# 4-SSR.net
KiCad netlist of a schematic drawn in EAGLE
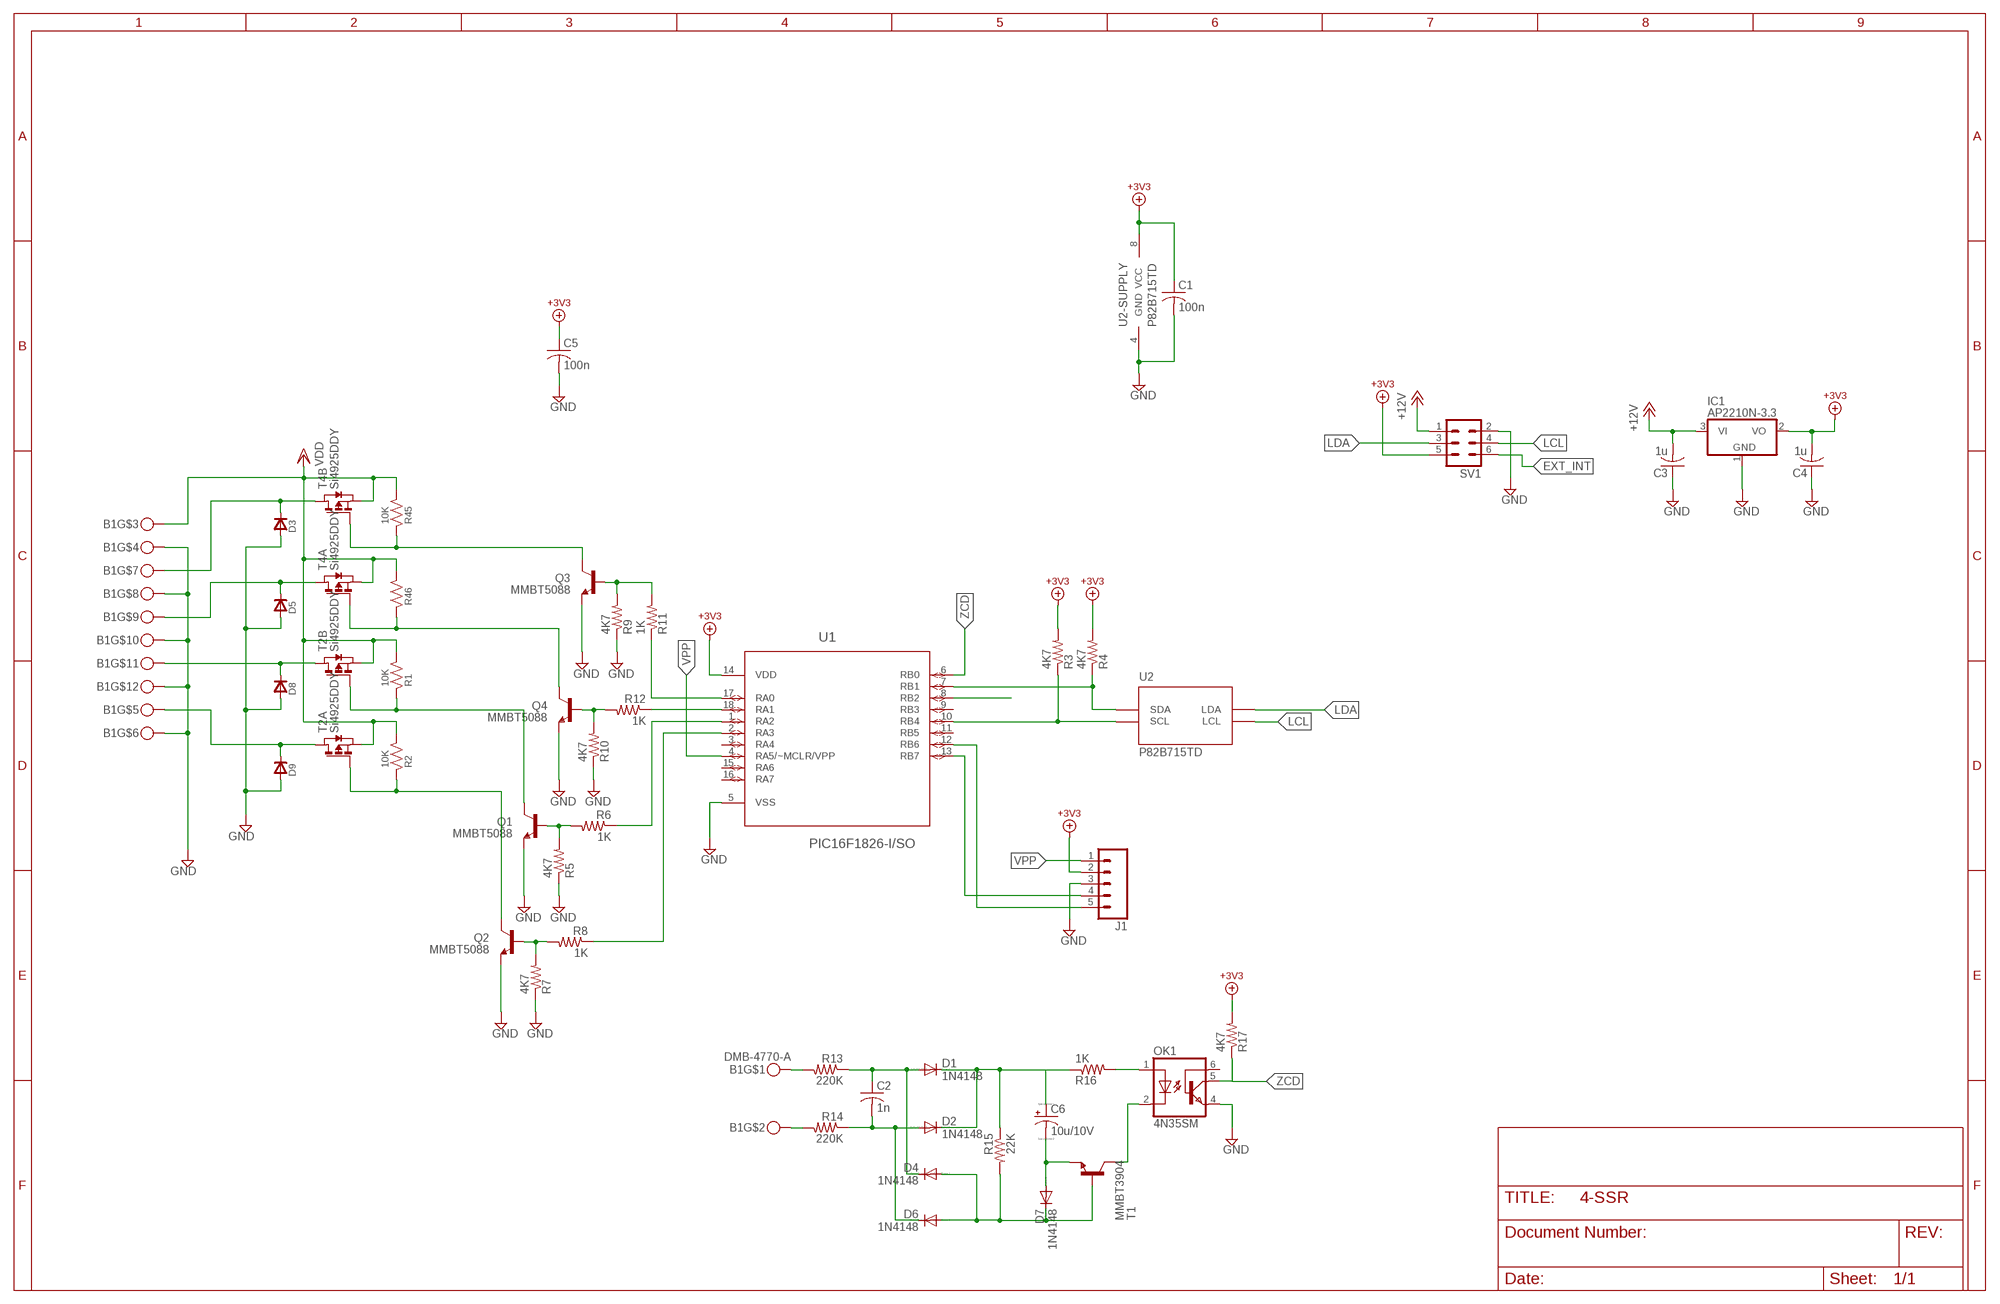
[diagram p0: schematic, sheet 1]

(export (version "E")
  (design (tool "Eeschema 10.0.6"))
  (components
    (comp (ref "B1")
      (value "DMB-4770-A")
      (footprint "eagle-import:DMB-4770-A-PKG")
      (libsource (lib "eagle-import") (part "DMB-4770-A"))
    )
    (comp (ref "C1")
      (value "100n")
      (footprint "eagle-import:C0805")
      (libsource (lib "eagle-import") (part "C-USC0805"))
    )
    (comp (ref "C2")
      (value "1n")
      (footprint "eagle-import:C1808")
      (libsource (lib "eagle-import") (part "C-USC1808"))
    )
    (comp (ref "C3")
      (value "1u")
      (footprint "eagle-import:C0805")
      (libsource (lib "eagle-import") (part "C-USC0805"))
    )
    (comp (ref "C4")
      (value "1u")
      (footprint "eagle-import:C0805")
      (libsource (lib "eagle-import") (part "C-USC0805"))
    )
    (comp (ref "C5")
      (value "100n")
      (footprint "eagle-import:C0805")
      (libsource (lib "eagle-import") (part "C-USC0805"))
    )
    (comp (ref "C6")
      (value "10u/10V")
      (footprint "eagle-import:PANASONIC_B")
      (libsource (lib "eagle-import") (part "CPOL-USB"))
    )
    (comp (ref "D1")
      (value "1N4148")
      (footprint "eagle-import:SOD80C")
      (libsource (lib "eagle-import") (part "DIODE-SOD80C"))
    )
    (comp (ref "D2")
      (value "1N4148")
      (footprint "eagle-import:SOD80C")
      (libsource (lib "eagle-import") (part "DIODE-SOD80C"))
    )
    (comp (ref "D3")
      (value "DSMA")
      (footprint "eagle-import:DSMA")
      (libsource (lib "eagle-import") (part "DSMA"))
    )
    (comp (ref "D4")
      (value "1N4148")
      (footprint "eagle-import:SOD80C")
      (libsource (lib "eagle-import") (part "DIODE-SOD80C"))
    )
    (comp (ref "D5")
      (value "DSMA")
      (footprint "eagle-import:DSMA")
      (libsource (lib "eagle-import") (part "DSMA"))
    )
    (comp (ref "D6")
      (value "1N4148")
      (footprint "eagle-import:SOD80C")
      (libsource (lib "eagle-import") (part "DIODE-SOD80C"))
    )
    (comp (ref "D7")
      (value "1N4148")
      (footprint "eagle-import:SOD80C")
      (libsource (lib "eagle-import") (part "DIODE-SOD80C"))
    )
    (comp (ref "D8")
      (value "DSMA")
      (footprint "eagle-import:DSMA")
      (libsource (lib "eagle-import") (part "DSMA"))
    )
    (comp (ref "D9")
      (value "DSMA")
      (footprint "eagle-import:DSMA")
      (libsource (lib "eagle-import") (part "DSMA"))
    )
    (comp (ref "IC1")
      (value "AP2210N-3.3")
      (footprint "eagle-import:SOT23")
      (libsource (lib "eagle-import") (part "MCP1703CB"))
    )
    (comp (ref "J1")
      (value "M05PTH")
      (footprint "eagle-import:1X05")
      (libsource (lib "eagle-import") (part "M05PTH"))
    )
    (comp (ref "OK1")
      (value "4N35SM")
      (footprint "eagle-import:DIL6-SMD")
      (fields (field (name "MF") "FAIRCHILD SEMICONDUCTOR") (field (name "MPN") "4N35S-M"))
      (libsource (lib "eagle-import") (part "4N?MS35"))
    )
    (comp (ref "Q1")
      (value "MMBT5088")
      (footprint "eagle-import:SOT23-3")
      (libsource (lib "eagle-import") (part "TRANSISTOR_NPNMMBT5088"))
    )
    (comp (ref "Q2")
      (value "MMBT5088")
      (footprint "eagle-import:SOT23-3")
      (libsource (lib "eagle-import") (part "TRANSISTOR_NPNMMBT5088"))
    )
    (comp (ref "Q3")
      (value "MMBT5088")
      (footprint "eagle-import:SOT23-3")
      (libsource (lib "eagle-import") (part "TRANSISTOR_NPNMMBT5088"))
    )
    (comp (ref "Q4")
      (value "MMBT5088")
      (footprint "eagle-import:SOT23-3")
      (libsource (lib "eagle-import") (part "TRANSISTOR_NPNMMBT5088"))
    )
    (comp (ref "R1")
      (value "10K")
      (footprint "eagle-import:R0805")
      (libsource (lib "eagle-import") (part "RU0805"))
    )
    (comp (ref "R2")
      (value "10K")
      (footprint "eagle-import:R0805")
      (libsource (lib "eagle-import") (part "RU0805"))
    )
    (comp (ref "R3")
      (value "4K7")
      (footprint "eagle-import:R0805")
      (libsource (lib "eagle-import") (part "resistor_R-US_R0805"))
    )
    (comp (ref "R4")
      (value "4K7")
      (footprint "eagle-import:R0805")
      (libsource (lib "eagle-import") (part "resistor_R-US_R0805"))
    )
    (comp (ref "R5")
      (value "4K7")
      (footprint "eagle-import:R0805")
      (libsource (lib "eagle-import") (part "resistor_R-US_R0805"))
    )
    (comp (ref "R6")
      (value "1K")
      (footprint "eagle-import:R0805")
      (libsource (lib "eagle-import") (part "resistor_R-US_R0805"))
    )
    (comp (ref "R7")
      (value "4K7")
      (footprint "eagle-import:R0805")
      (libsource (lib "eagle-import") (part "resistor_R-US_R0805"))
    )
    (comp (ref "R8")
      (value "1K")
      (footprint "eagle-import:R0805")
      (libsource (lib "eagle-import") (part "resistor_R-US_R0805"))
    )
    (comp (ref "R9")
      (value "4K7")
      (footprint "eagle-import:R0805")
      (libsource (lib "eagle-import") (part "resistor_R-US_R0805"))
    )
    (comp (ref "R10")
      (value "4K7")
      (footprint "eagle-import:R0805")
      (libsource (lib "eagle-import") (part "resistor_R-US_R0805"))
    )
    (comp (ref "R11")
      (value "1K")
      (footprint "eagle-import:R0805")
      (libsource (lib "eagle-import") (part "resistor_R-US_R0805"))
    )
    (comp (ref "R12")
      (value "1K")
      (footprint "eagle-import:R0805")
      (libsource (lib "eagle-import") (part "resistor_R-US_R0805"))
    )
    (comp (ref "R13")
      (value "220K")
      (footprint "eagle-import:R0805")
      (libsource (lib "eagle-import") (part "R-US_R0805"))
    )
    (comp (ref "R14")
      (value "220K")
      (footprint "eagle-import:R0805")
      (libsource (lib "eagle-import") (part "R-US_R0805"))
    )
    (comp (ref "R15")
      (value "22K")
      (footprint "eagle-import:R0805")
      (libsource (lib "eagle-import") (part "R-US_R0805"))
    )
    (comp (ref "R16")
      (value "1K")
      (footprint "eagle-import:R0805")
      (libsource (lib "eagle-import") (part "R-US_R0805"))
    )
    (comp (ref "R17")
      (value "4K7")
      (footprint "eagle-import:R0805")
      (libsource (lib "eagle-import") (part "resistor_R-US_R0805"))
    )
    (comp (ref "R45")
      (value "10K")
      (footprint "eagle-import:R0805")
      (libsource (lib "eagle-import") (part "RU0805"))
    )
    (comp (ref "R46")
      (value "RU0805")
      (footprint "eagle-import:R0805")
      (libsource (lib "eagle-import") (part "RU0805"))
    )
    (comp (ref "SV1")
      (value "ML6")
      (footprint "eagle-import:ML6")
      (libsource (lib "eagle-import") (part "ML6"))
    )
    (comp (ref "T1")
      (value "MMBT3904")
      (footprint "eagle-import:SOT23-BEC")
      (libsource (lib "eagle-import") (part "-NPN-SOT23-BECMMBT3904LT1"))
    )
    (comp (ref "T2")
      (value "Si4925DDY")
      (footprint "eagle-import:SO8")
      (libsource (lib "eagle-import") (part "PMOS2SO8"))
    )
    (comp (ref "T4")
      (value "Si4925DDY")
      (footprint "eagle-import:SO8")
      (libsource (lib "eagle-import") (part "PMOS2SO8"))
    )
    (comp (ref "U1")
      (value "PIC16F1826-I/SO")
      (footprint "eagle-import:SOIC127P1030X175-18N")
      (libsource (lib "eagle-import") (part "PIC16F1826-I/SO"))
    )
    (comp (ref "U2")
      (value "P82B715TD")
      (footprint "eagle-import:SOIC-8")
      (fields (field (name "MANUFACTURER") "NXP Semiconductors") (field (name "PART_NUMBER") "P82B715TD,118"))
      (libsource (lib "eagle-import") (part "P82B715?TD"))
    )
  )
  (nets
    (net (code "1") (name "+12V") (class "Default")
      (node (ref "C3") (pin "2") (pinfunction "2_2") (pintype "passive"))
      (node (ref "IC1") (pin "3") (pinfunction "VI_3") (pintype "input"))
      (node (ref "SV1") (pin "1") (pinfunction "1_1") (pintype "passive"))
    )
    (net (code "2") (name "EXT_INT") (class "Default")
      (node (ref "SV1") (pin "6") (pinfunction "6_6") (pintype "passive"))
    )
    (net (code "3") (name "GND") (class "Default")
      (node (ref "B1") (pin "P$10") (pinfunction "KL_P$10") (pintype "passive"))
      (node (ref "B1") (pin "P$12") (pinfunction "KL_P$12") (pintype "passive"))
      (node (ref "B1") (pin "P$4") (pinfunction "KL_P$4") (pintype "passive"))
      (node (ref "B1") (pin "P$6") (pinfunction "KL_P$6") (pintype "passive"))
      (node (ref "B1") (pin "P$8") (pinfunction "KL_P$8") (pintype "passive"))
      (node (ref "C1") (pin "2") (pinfunction "2_2") (pintype "passive"))
      (node (ref "C3") (pin "1") (pinfunction "1_1") (pintype "passive"))
      (node (ref "C4") (pin "1") (pinfunction "1_1") (pintype "passive"))
      (node (ref "C5") (pin "2") (pinfunction "2_2") (pintype "passive"))
      (node (ref "D3") (pin "A") (pinfunction "A_A") (pintype "passive"))
      (node (ref "D5") (pin "A") (pinfunction "A_A") (pintype "passive"))
      (node (ref "D8") (pin "A") (pinfunction "A_A") (pintype "passive"))
      (node (ref "D9") (pin "A") (pinfunction "A_A") (pintype "passive"))
      (node (ref "IC1") (pin "1") (pinfunction "GND_1") (pintype "passive"))
      (node (ref "J1") (pin "3") (pinfunction "3_3") (pintype "passive"))
      (node (ref "OK1") (pin "4") (pinfunction "EMI_4") (pintype "passive"))
      (node (ref "Q1") (pin "2") (pinfunction "E_2") (pintype "passive"))
      (node (ref "Q2") (pin "2") (pinfunction "E_2") (pintype "passive"))
      (node (ref "Q3") (pin "2") (pinfunction "E_2") (pintype "passive"))
      (node (ref "Q4") (pin "2") (pinfunction "E_2") (pintype "passive"))
      (node (ref "R10") (pin "1") (pinfunction "1_1") (pintype "passive"))
      (node (ref "R5") (pin "1") (pinfunction "1_1") (pintype "passive"))
      (node (ref "R7") (pin "1") (pinfunction "1_1") (pintype "passive"))
      (node (ref "R9") (pin "1") (pinfunction "1_1") (pintype "passive"))
      (node (ref "SV1") (pin "2") (pinfunction "2_2") (pintype "passive"))
      (node (ref "U1") (pin "5") (pinfunction "VSS_5") (pintype "power_in"))
      (node (ref "U2") (pin "4") (pinfunction "GND_4") (pintype "bidirectional"))
    )
    (net (code "4") (name "LCL") (class "Default")
      (node (ref "SV1") (pin "4") (pinfunction "4_4") (pintype "passive"))
      (node (ref "U2") (pin "2") (pinfunction "LCL_2") (pintype "bidirectional"))
    )
    (net (code "5") (name "LDA") (class "Default")
      (node (ref "SV1") (pin "3") (pinfunction "3_3") (pintype "passive"))
      (node (ref "U2") (pin "7") (pinfunction "LDA_7") (pintype "bidirectional"))
    )
    (net (code "6") (name "Net-(B1A-KL)") (class "Default")
      (node (ref "B1") (pin "P$1") (pinfunction "KL_P$1") (pintype "passive"))
      (node (ref "R13") (pin "2") (pinfunction "2_2") (pintype "passive"))
    )
    (net (code "7") (name "Net-(B1C-KL)") (class "Default")
      (node (ref "B1") (pin "P$11") (pinfunction "KL_P$11") (pintype "passive"))
      (node (ref "D8") (pin "C") (pinfunction "C_C") (pintype "passive"))
      (node (ref "T2") (pin "5") (pinfunction "D_5") (pintype "passive"))
      (node (ref "T2") (pin "6") (pinfunction "D_6") (pintype "passive"))
    )
    (net (code "8") (name "Net-(B1E-KL)") (class "Default")
      (node (ref "B1") (pin "P$2") (pinfunction "KL_P$2") (pintype "passive"))
      (node (ref "R14") (pin "2") (pinfunction "2_2") (pintype "passive"))
    )
    (net (code "9") (name "Net-(B1H-KL)") (class "Default")
      (node (ref "B1") (pin "P$5") (pinfunction "KL_P$5") (pintype "passive"))
      (node (ref "D9") (pin "C") (pinfunction "C_C") (pintype "passive"))
      (node (ref "T2") (pin "7") (pinfunction "D_7") (pintype "passive"))
      (node (ref "T2") (pin "8") (pinfunction "D_8") (pintype "passive"))
    )
    (net (code "10") (name "Net-(B1J-KL)") (class "Default")
      (node (ref "B1") (pin "P$7") (pinfunction "KL_P$7") (pintype "passive"))
      (node (ref "D3") (pin "C") (pinfunction "C_C") (pintype "passive"))
      (node (ref "T4") (pin "5") (pinfunction "D_5") (pintype "passive"))
      (node (ref "T4") (pin "6") (pinfunction "D_6") (pintype "passive"))
    )
    (net (code "11") (name "Net-(B1L-KL)") (class "Default")
      (node (ref "B1") (pin "P$9") (pinfunction "KL_P$9") (pintype "passive"))
      (node (ref "D5") (pin "C") (pinfunction "C_C") (pintype "passive"))
      (node (ref "T4") (pin "7") (pinfunction "D_7") (pintype "passive"))
      (node (ref "T4") (pin "8") (pinfunction "D_8") (pintype "passive"))
    )
    (net (code "12") (name "Net-(C2-Pad1)") (class "Default")
      (node (ref "C2") (pin "1") (pinfunction "1_1") (pintype "passive"))
      (node (ref "D1") (pin "A") (pinfunction "A_A") (pintype "passive"))
      (node (ref "D4") (pin "C") (pinfunction "C_C") (pintype "passive"))
      (node (ref "R13") (pin "1") (pinfunction "1_1") (pintype "passive"))
    )
    (net (code "13") (name "Net-(C2-Pad2)") (class "Default")
      (node (ref "C2") (pin "2") (pinfunction "2_2") (pintype "passive"))
      (node (ref "D2") (pin "A") (pinfunction "A_A") (pintype "passive"))
      (node (ref "D6") (pin "C") (pinfunction "C_C") (pintype "passive"))
      (node (ref "R14") (pin "1") (pinfunction "1_1") (pintype "passive"))
    )
    (net (code "14") (name "Net-(C6-Pad+)") (class "Default")
      (node (ref "C6") (pin "+") (pinfunction "+_+") (pintype "passive"))
      (node (ref "D1") (pin "C") (pinfunction "C_C") (pintype "passive"))
      (node (ref "D2") (pin "C") (pinfunction "C_C") (pintype "passive"))
      (node (ref "R15") (pin "1") (pinfunction "1_1") (pintype "passive"))
      (node (ref "R16") (pin "1") (pinfunction "1_1") (pintype "passive"))
    )
    (net (code "15") (name "Net-(C6-Pad-)") (class "Default")
      (node (ref "C6") (pin "-") (pinfunction "-_-") (pintype "passive"))
      (node (ref "D7") (pin "A") (pinfunction "A_A") (pintype "passive"))
      (node (ref "T1") (pin "E") (pinfunction "E_E") (pintype "passive"))
    )
    (net (code "16") (name "Net-(D4-PadA)") (class "Default")
      (node (ref "D4") (pin "A") (pinfunction "A_A") (pintype "passive"))
      (node (ref "D6") (pin "A") (pinfunction "A_A") (pintype "passive"))
      (node (ref "D7") (pin "C") (pinfunction "C_C") (pintype "passive"))
      (node (ref "R15") (pin "2") (pinfunction "2_2") (pintype "passive"))
      (node (ref "T1") (pin "B") (pinfunction "B_B") (pintype "passive"))
    )
    (net (code "17") (name "Net-(OK1-A)") (class "Default")
      (node (ref "OK1") (pin "1") (pinfunction "A_1") (pintype "passive"))
      (node (ref "R16") (pin "2") (pinfunction "2_2") (pintype "passive"))
    )
    (net (code "18") (name "Net-(OK1-C)") (class "Default")
      (node (ref "OK1") (pin "2") (pinfunction "C_2") (pintype "passive"))
      (node (ref "T1") (pin "C") (pinfunction "C_C") (pintype "passive"))
    )
    (net (code "19") (name "Net-(Q1-B)") (class "Default")
      (node (ref "Q1") (pin "1") (pinfunction "B_1") (pintype "passive"))
      (node (ref "R5") (pin "2") (pinfunction "2_2") (pintype "passive"))
      (node (ref "R6") (pin "2") (pinfunction "2_2") (pintype "passive"))
    )
    (net (code "20") (name "Net-(Q1-C)") (class "Default")
      (node (ref "Q1") (pin "3") (pinfunction "C_3") (pintype "passive"))
      (node (ref "R1") (pin "1") (pinfunction "1_1") (pintype "passive"))
      (node (ref "T2") (pin "4") (pinfunction "G_4") (pintype "passive"))
    )
    (net (code "21") (name "Net-(Q2-B)") (class "Default")
      (node (ref "Q2") (pin "1") (pinfunction "B_1") (pintype "passive"))
      (node (ref "R7") (pin "2") (pinfunction "2_2") (pintype "passive"))
      (node (ref "R8") (pin "2") (pinfunction "2_2") (pintype "passive"))
    )
    (net (code "22") (name "Net-(Q2-C)") (class "Default")
      (node (ref "Q2") (pin "3") (pinfunction "C_3") (pintype "passive"))
      (node (ref "R2") (pin "1") (pinfunction "1_1") (pintype "passive"))
      (node (ref "T2") (pin "2") (pinfunction "G_2") (pintype "passive"))
    )
    (net (code "23") (name "Net-(Q3-B)") (class "Default")
      (node (ref "Q3") (pin "1") (pinfunction "B_1") (pintype "passive"))
      (node (ref "R11") (pin "2") (pinfunction "2_2") (pintype "passive"))
      (node (ref "R9") (pin "2") (pinfunction "2_2") (pintype "passive"))
    )
    (net (code "24") (name "Net-(Q3-C)") (class "Default")
      (node (ref "Q3") (pin "3") (pinfunction "C_3") (pintype "passive"))
      (node (ref "R45") (pin "1") (pinfunction "1_1") (pintype "passive"))
      (node (ref "T4") (pin "4") (pinfunction "G_4") (pintype "passive"))
    )
    (net (code "25") (name "Net-(Q4-B)") (class "Default")
      (node (ref "Q4") (pin "1") (pinfunction "B_1") (pintype "passive"))
      (node (ref "R10") (pin "2") (pinfunction "2_2") (pintype "passive"))
      (node (ref "R12") (pin "2") (pinfunction "2_2") (pintype "passive"))
    )
    (net (code "26") (name "Net-(Q4-C)") (class "Default")
      (node (ref "Q4") (pin "3") (pinfunction "C_3") (pintype "passive"))
      (node (ref "R46") (pin "1") (pinfunction "1_1") (pintype "passive"))
      (node (ref "T4") (pin "2") (pinfunction "G_2") (pintype "passive"))
    )
    (net (code "27") (name "Net-(U1-RA0)") (class "Default")
      (node (ref "R11") (pin "1") (pinfunction "1_1") (pintype "passive"))
      (node (ref "U1") (pin "17") (pinfunction "RA0_17") (pintype "bidirectional"))
    )
    (net (code "28") (name "Net-(U1-RA1)") (class "Default")
      (node (ref "R12") (pin "1") (pinfunction "1_1") (pintype "passive"))
      (node (ref "U1") (pin "18") (pinfunction "RA1_18") (pintype "bidirectional"))
    )
    (net (code "29") (name "Net-(U1-RA2)") (class "Default")
      (node (ref "R6") (pin "1") (pinfunction "1_1") (pintype "passive"))
      (node (ref "U1") (pin "1") (pinfunction "RA2_1") (pintype "bidirectional"))
    )
    (net (code "30") (name "Net-(U1-RA3)") (class "Default")
      (node (ref "R8") (pin "1") (pinfunction "1_1") (pintype "passive"))
      (node (ref "U1") (pin "2") (pinfunction "RA3_2") (pintype "bidirectional"))
    )
    (net (code "31") (name "Net-(U1-RB1)") (class "Default")
      (node (ref "R4") (pin "1") (pinfunction "1_1") (pintype "passive"))
      (node (ref "U1") (pin "7") (pinfunction "RB1_7") (pintype "bidirectional"))
      (node (ref "U2") (pin "6") (pinfunction "SDA_6") (pintype "bidirectional"))
    )
    (net (code "32") (name "Net-(U1-RB4)") (class "Default")
      (node (ref "R3") (pin "1") (pinfunction "1_1") (pintype "passive"))
      (node (ref "U1") (pin "10") (pinfunction "RB4_10") (pintype "bidirectional"))
      (node (ref "U2") (pin "3") (pinfunction "SCL_3") (pintype "bidirectional"))
    )
    (net (code "33") (name "Net-(U1-RB6)") (class "Default")
      (node (ref "J1") (pin "5") (pinfunction "5_5") (pintype "passive"))
      (node (ref "U1") (pin "12") (pinfunction "RB6_12") (pintype "bidirectional"))
    )
    (net (code "34") (name "Net-(U1-RB7)") (class "Default")
      (node (ref "J1") (pin "4") (pinfunction "4_4") (pintype "passive"))
      (node (ref "U1") (pin "13") (pinfunction "RB7_13") (pintype "bidirectional"))
    )
    (net (code "35") (name "V+3V3") (class "Default")
      (node (ref "C1") (pin "1") (pinfunction "1_1") (pintype "passive"))
      (node (ref "C4") (pin "2") (pinfunction "2_2") (pintype "passive"))
      (node (ref "C5") (pin "1") (pinfunction "1_1") (pintype "passive"))
      (node (ref "IC1") (pin "2") (pinfunction "VO_2") (pintype "passive"))
      (node (ref "J1") (pin "2") (pinfunction "2_2") (pintype "passive"))
      (node (ref "R17") (pin "2") (pinfunction "2_2") (pintype "passive"))
      (node (ref "R3") (pin "2") (pinfunction "2_2") (pintype "passive"))
      (node (ref "R4") (pin "2") (pinfunction "2_2") (pintype "passive"))
      (node (ref "SV1") (pin "5") (pinfunction "5_5") (pintype "passive"))
      (node (ref "U1") (pin "14") (pinfunction "VDD_14") (pintype "power_in"))
      (node (ref "U2") (pin "8") (pinfunction "VCC_8") (pintype "bidirectional"))
    )
    (net (code "36") (name "VDD") (class "Default")
      (node (ref "B1") (pin "P$3") (pinfunction "KL_P$3") (pintype "passive"))
      (node (ref "R1") (pin "2") (pinfunction "2_2") (pintype "passive"))
      (node (ref "R2") (pin "2") (pinfunction "2_2") (pintype "passive"))
      (node (ref "R45") (pin "2") (pinfunction "2_2") (pintype "passive"))
      (node (ref "R46") (pin "2") (pinfunction "2_2") (pintype "passive"))
      (node (ref "T2") (pin "1") (pinfunction "S_1") (pintype "passive"))
      (node (ref "T2") (pin "3") (pinfunction "S_3") (pintype "passive"))
      (node (ref "T4") (pin "1") (pinfunction "S_1") (pintype "passive"))
      (node (ref "T4") (pin "3") (pinfunction "S_3") (pintype "passive"))
    )
    (net (code "37") (name "VPP") (class "Default")
      (node (ref "J1") (pin "1") (pinfunction "1_1") (pintype "passive"))
      (node (ref "U1") (pin "4") (pinfunction "RA5/~{MCLR/VPP}_4") (pintype "bidirectional"))
    )
    (net (code "38") (name "ZCD") (class "Default")
      (node (ref "OK1") (pin "5") (pinfunction "COL_5") (pintype "passive"))
      (node (ref "R17") (pin "1") (pinfunction "1_1") (pintype "passive"))
      (node (ref "U1") (pin "6") (pinfunction "RB0_6") (pintype "bidirectional"))
    )
    (net (code "39") (name "unconnected-(OK1-BAS-Pad6)") (class "Default")
      (node (ref "OK1") (pin "6") (pinfunction "BAS_6") (pintype "passive"))
    )
    (net (code "40") (name "unconnected-(U1-RA4-Pad3)") (class "Default")
      (node (ref "U1") (pin "3") (pinfunction "RA4_3") (pintype "bidirectional"))
    )
    (net (code "41") (name "unconnected-(U1-RA6-Pad15)") (class "Default")
      (node (ref "U1") (pin "15") (pinfunction "RA6_15") (pintype "bidirectional"))
    )
    (net (code "42") (name "unconnected-(U1-RA7-Pad16)") (class "Default")
      (node (ref "U1") (pin "16") (pinfunction "RA7_16") (pintype "bidirectional"))
    )
    (net (code "43") (name "unconnected-(U1-RB2-Pad8)") (class "Default")
      (node (ref "U1") (pin "8") (pinfunction "RB2_8") (pintype "bidirectional"))
    )
    (net (code "44") (name "unconnected-(U1-RB3-Pad9)") (class "Default")
      (node (ref "U1") (pin "9") (pinfunction "RB3_9") (pintype "bidirectional"))
    )
    (net (code "45") (name "unconnected-(U1-RB5-Pad11)") (class "Default")
      (node (ref "U1") (pin "11") (pinfunction "RB5_11") (pintype "bidirectional"))
    )
  )
)
